# bluepill-knx-transceiver.net
KiCad netlist of a schematic drawn in EAGLE
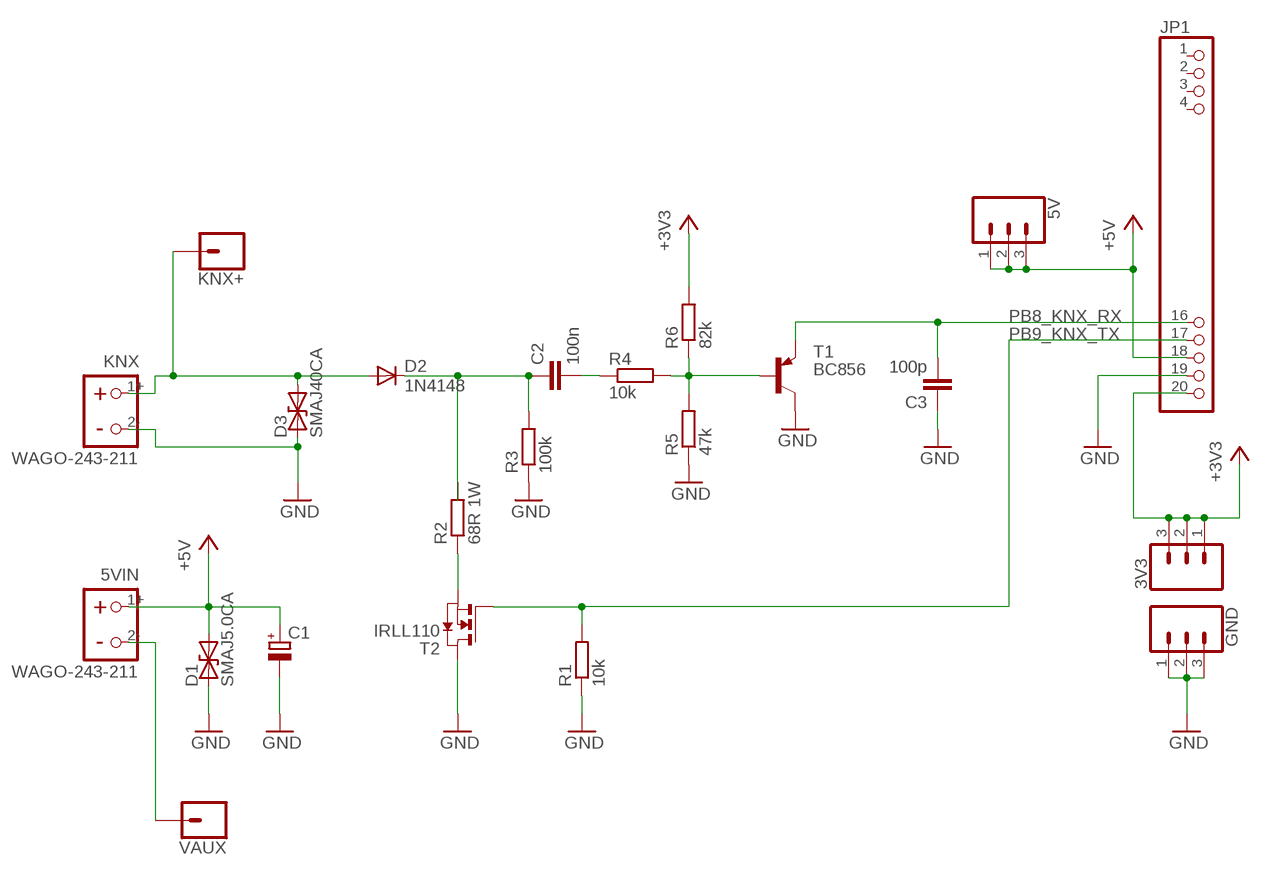
[diagram p0: schematic, sheet 1]

(export (version "E")
  (design (tool "Eeschema 10.0.6"))
  (components
    (comp (ref "3V3")
      (value "CONN_03")
      (footprint "eagle-import:1X03")
      (libsource (lib "eagle-import") (part "CONN_03"))
    )
    (comp (ref "5V")
      (value "CONN_03")
      (footprint "eagle-import:1X03")
      (libsource (lib "eagle-import") (part "CONN_03"))
    )
    (comp (ref "5VIN")
      (value "WAGO-243-211")
      (footprint "eagle-import:WAGO-243-211")
      (libsource (lib "eagle-import") (part "WAGO-243-211"))
    )
    (comp (ref "C1")
      (value "CPOL-EUE3.5-8")
      (footprint "eagle-import:E3,5-8")
      (libsource (lib "eagle-import") (part "CPOL-EUE3.5-8"))
    )
    (comp (ref "C2")
      (value "100n")
      (footprint "eagle-import:C1206")
      (libsource (lib "eagle-import") (part "C-EUC1206"))
    )
    (comp (ref "C3")
      (value "100p")
      (footprint "eagle-import:C1206")
      (libsource (lib "eagle-import") (part "C-EUC1206"))
    )
    (comp (ref "D1")
      (value "SMAJ5.0CA")
      (footprint "eagle-import:DO-214AC")
      (libsource (lib "eagle-import") (part "SMAJ40AC"))
    )
    (comp (ref "D2")
      (value "1N4148")
      (footprint "eagle-import:MINIMELF")
      (libsource (lib "eagle-import") (part "DIODE-MINIMELF"))
    )
    (comp (ref "D3")
      (value "SMAJ40CA")
      (footprint "eagle-import:DO-214AC")
      (libsource (lib "eagle-import") (part "SMAJ40AC"))
    )
    (comp (ref "GND")
      (value "CONN_03")
      (footprint "eagle-import:1X03")
      (libsource (lib "eagle-import") (part "CONN_03"))
    )
    (comp (ref "JP1")
      (value "PINHD-1X20-BP")
      (footprint "eagle-import:1X20-BP")
      (libsource (lib "eagle-import") (part "PINHD-1X20-BP"))
    )
    (comp (ref "KNX")
      (value "WAGO-243-211")
      (footprint "eagle-import:WAGO-243-211")
      (libsource (lib "eagle-import") (part "WAGO-243-211"))
    )
    (comp (ref "KNX+")
      (value "CONN_01")
      (footprint "eagle-import:1X01")
      (libsource (lib "eagle-import") (part "CONN_01"))
    )
    (comp (ref "R1")
      (value "10k")
      (footprint "eagle-import:R1206")
      (libsource (lib "eagle-import") (part "R-EU_R1206"))
    )
    (comp (ref "R2")
      (value "68R 1W")
      (footprint "eagle-import:R2512")
      (libsource (lib "eagle-import") (part "rcl_334_R-EU_R2512"))
    )
    (comp (ref "R3")
      (value "100k")
      (footprint "eagle-import:R1206")
      (libsource (lib "eagle-import") (part "R-EU_R1206"))
    )
    (comp (ref "R4")
      (value "10k")
      (footprint "eagle-import:R1206")
      (libsource (lib "eagle-import") (part "R-EU_R1206"))
    )
    (comp (ref "R5")
      (value "47k")
      (footprint "eagle-import:R1206")
      (libsource (lib "eagle-import") (part "R-EU_R1206"))
    )
    (comp (ref "R6")
      (value "82k")
      (footprint "eagle-import:R1206")
      (libsource (lib "eagle-import") (part "R-EU_R1206"))
    )
    (comp (ref "T1")
      (value "BC856")
      (footprint "eagle-import:SOT23-BEC")
      (libsource (lib "eagle-import") (part "BC856SMDB"))
    )
    (comp (ref "T2")
      (value "IRLL110")
      (footprint "eagle-import:SOT223")
      (libsource (lib "eagle-import") (part "NMOSSOT223"))
    )
    (comp (ref "VAUX")
      (value "CONN_01")
      (footprint "eagle-import:1X01")
      (libsource (lib "eagle-import") (part "CONN_01"))
    )
  )
  (nets
    (net (code "1") (name "+3V3") (class "Default")
      (node (ref "3V3") (pin "1") (pinfunction "1_1") (pintype "passive"))
      (node (ref "3V3") (pin "2") (pinfunction "2_2") (pintype "passive"))
      (node (ref "3V3") (pin "3") (pinfunction "3_3") (pintype "passive"))
      (node (ref "JP1") (pin "20") (pinfunction "20_20") (pintype "passive"))
      (node (ref "R6") (pin "2") (pinfunction "2_2") (pintype "passive"))
    )
    (net (code "2") (name "+5V") (class "Default")
      (node (ref "5V") (pin "1") (pinfunction "1_1") (pintype "passive"))
      (node (ref "5V") (pin "2") (pinfunction "2_2") (pintype "passive"))
      (node (ref "5V") (pin "3") (pinfunction "3_3") (pintype "passive"))
      (node (ref "5VIN") (pin "1+") (pinfunction "1+_1+") (pintype "passive"))
      (node (ref "C1") (pin "+") (pinfunction "+_+") (pintype "passive"))
      (node (ref "D1") (pin "C") (pinfunction "C_C") (pintype "passive"))
      (node (ref "JP1") (pin "18") (pinfunction "18_18") (pintype "passive"))
    )
    (net (code "3") (name "/PB8_KNX_RX") (class "Default")
      (node (ref "C3") (pin "2") (pinfunction "2_2") (pintype "passive"))
      (node (ref "JP1") (pin "16") (pinfunction "16_16") (pintype "passive"))
      (node (ref "T1") (pin "E") (pinfunction "E_E") (pintype "passive"))
    )
    (net (code "4") (name "/PB9_KNX_TX") (class "Default")
      (node (ref "JP1") (pin "17") (pinfunction "17_17") (pintype "passive"))
      (node (ref "R1") (pin "2") (pinfunction "2_2") (pintype "passive"))
      (node (ref "T2") (pin "1") (pinfunction "G_1") (pintype "passive"))
    )
    (net (code "5") (name "GND") (class "Default")
      (node (ref "C1") (pin "-") (pinfunction "-_-") (pintype "passive"))
      (node (ref "C3") (pin "1") (pinfunction "1_1") (pintype "passive"))
      (node (ref "D1") (pin "A") (pinfunction "A_A") (pintype "passive"))
      (node (ref "D3") (pin "A") (pinfunction "A_A") (pintype "passive"))
      (node (ref "GND") (pin "1") (pinfunction "1_1") (pintype "passive"))
      (node (ref "GND") (pin "2") (pinfunction "2_2") (pintype "passive"))
      (node (ref "GND") (pin "3") (pinfunction "3_3") (pintype "passive"))
      (node (ref "JP1") (pin "19") (pinfunction "19_19") (pintype "passive"))
      (node (ref "KNX") (pin "2-") (pinfunction "2-_2-") (pintype "passive"))
      (node (ref "R1") (pin "1") (pinfunction "1_1") (pintype "passive"))
      (node (ref "R3") (pin "1") (pinfunction "1_1") (pintype "passive"))
      (node (ref "R5") (pin "1") (pinfunction "1_1") (pintype "passive"))
      (node (ref "T1") (pin "C") (pinfunction "C_C") (pintype "passive"))
      (node (ref "T2") (pin "2") (pinfunction "D_2") (pintype "passive"))
      (node (ref "T2") (pin "4") (pinfunction "D_4") (pintype "passive"))
    )
    (net (code "6") (name "Net-(5VIN-Pad2-)") (class "Default")
      (node (ref "5VIN") (pin "2-") (pinfunction "2-_2-") (pintype "passive"))
      (node (ref "VAUX") (pin "1") (pinfunction "1_1") (pintype "passive"))
    )
    (net (code "7") (name "Net-(C2-Pad1)") (class "Default")
      (node (ref "C2") (pin "1") (pinfunction "1_1") (pintype "passive"))
      (node (ref "D2") (pin "C") (pinfunction "C_C") (pintype "passive"))
      (node (ref "R2") (pin "2") (pinfunction "2_2") (pintype "passive"))
      (node (ref "R3") (pin "2") (pinfunction "2_2") (pintype "passive"))
    )
    (net (code "8") (name "Net-(C2-Pad2)") (class "Default")
      (node (ref "C2") (pin "2") (pinfunction "2_2") (pintype "passive"))
      (node (ref "R4") (pin "1") (pinfunction "1_1") (pintype "passive"))
    )
    (net (code "9") (name "Net-(D2-PadA)") (class "Default")
      (node (ref "D2") (pin "A") (pinfunction "A_A") (pintype "passive"))
      (node (ref "D3") (pin "C") (pinfunction "C_C") (pintype "passive"))
      (node (ref "KNX") (pin "1+") (pinfunction "1+_1+") (pintype "passive"))
      (node (ref "KNX+") (pin "1") (pinfunction "1_1") (pintype "passive"))
    )
    (net (code "10") (name "Net-(R4-Pad2)") (class "Default")
      (node (ref "R4") (pin "2") (pinfunction "2_2") (pintype "passive"))
      (node (ref "R5") (pin "2") (pinfunction "2_2") (pintype "passive"))
      (node (ref "R6") (pin "1") (pinfunction "1_1") (pintype "passive"))
      (node (ref "T1") (pin "B") (pinfunction "B_B") (pintype "passive"))
    )
    (net (code "11") (name "Net-(T2-S)") (class "Default")
      (node (ref "R2") (pin "1") (pinfunction "1_1") (pintype "passive"))
      (node (ref "T2") (pin "3") (pinfunction "S_3") (pintype "passive"))
    )
    (net (code "12") (name "unconnected-(JP1-Pad1)") (class "Default")
      (node (ref "JP1") (pin "1") (pinfunction "1_1") (pintype "passive"))
    )
    (net (code "13") (name "unconnected-(JP1-Pad2)") (class "Default")
      (node (ref "JP1") (pin "2") (pinfunction "2_2") (pintype "passive"))
    )
    (net (code "14") (name "unconnected-(JP1-Pad3)") (class "Default")
      (node (ref "JP1") (pin "3") (pinfunction "3_3") (pintype "passive"))
    )
    (net (code "15") (name "unconnected-(JP1-Pad4)") (class "Default")
      (node (ref "JP1") (pin "4") (pinfunction "4_4") (pintype "passive"))
    )
  )
)
